# UKU20710_power_board.net
KiCad netlist of a schematic drawn in Altium Designer
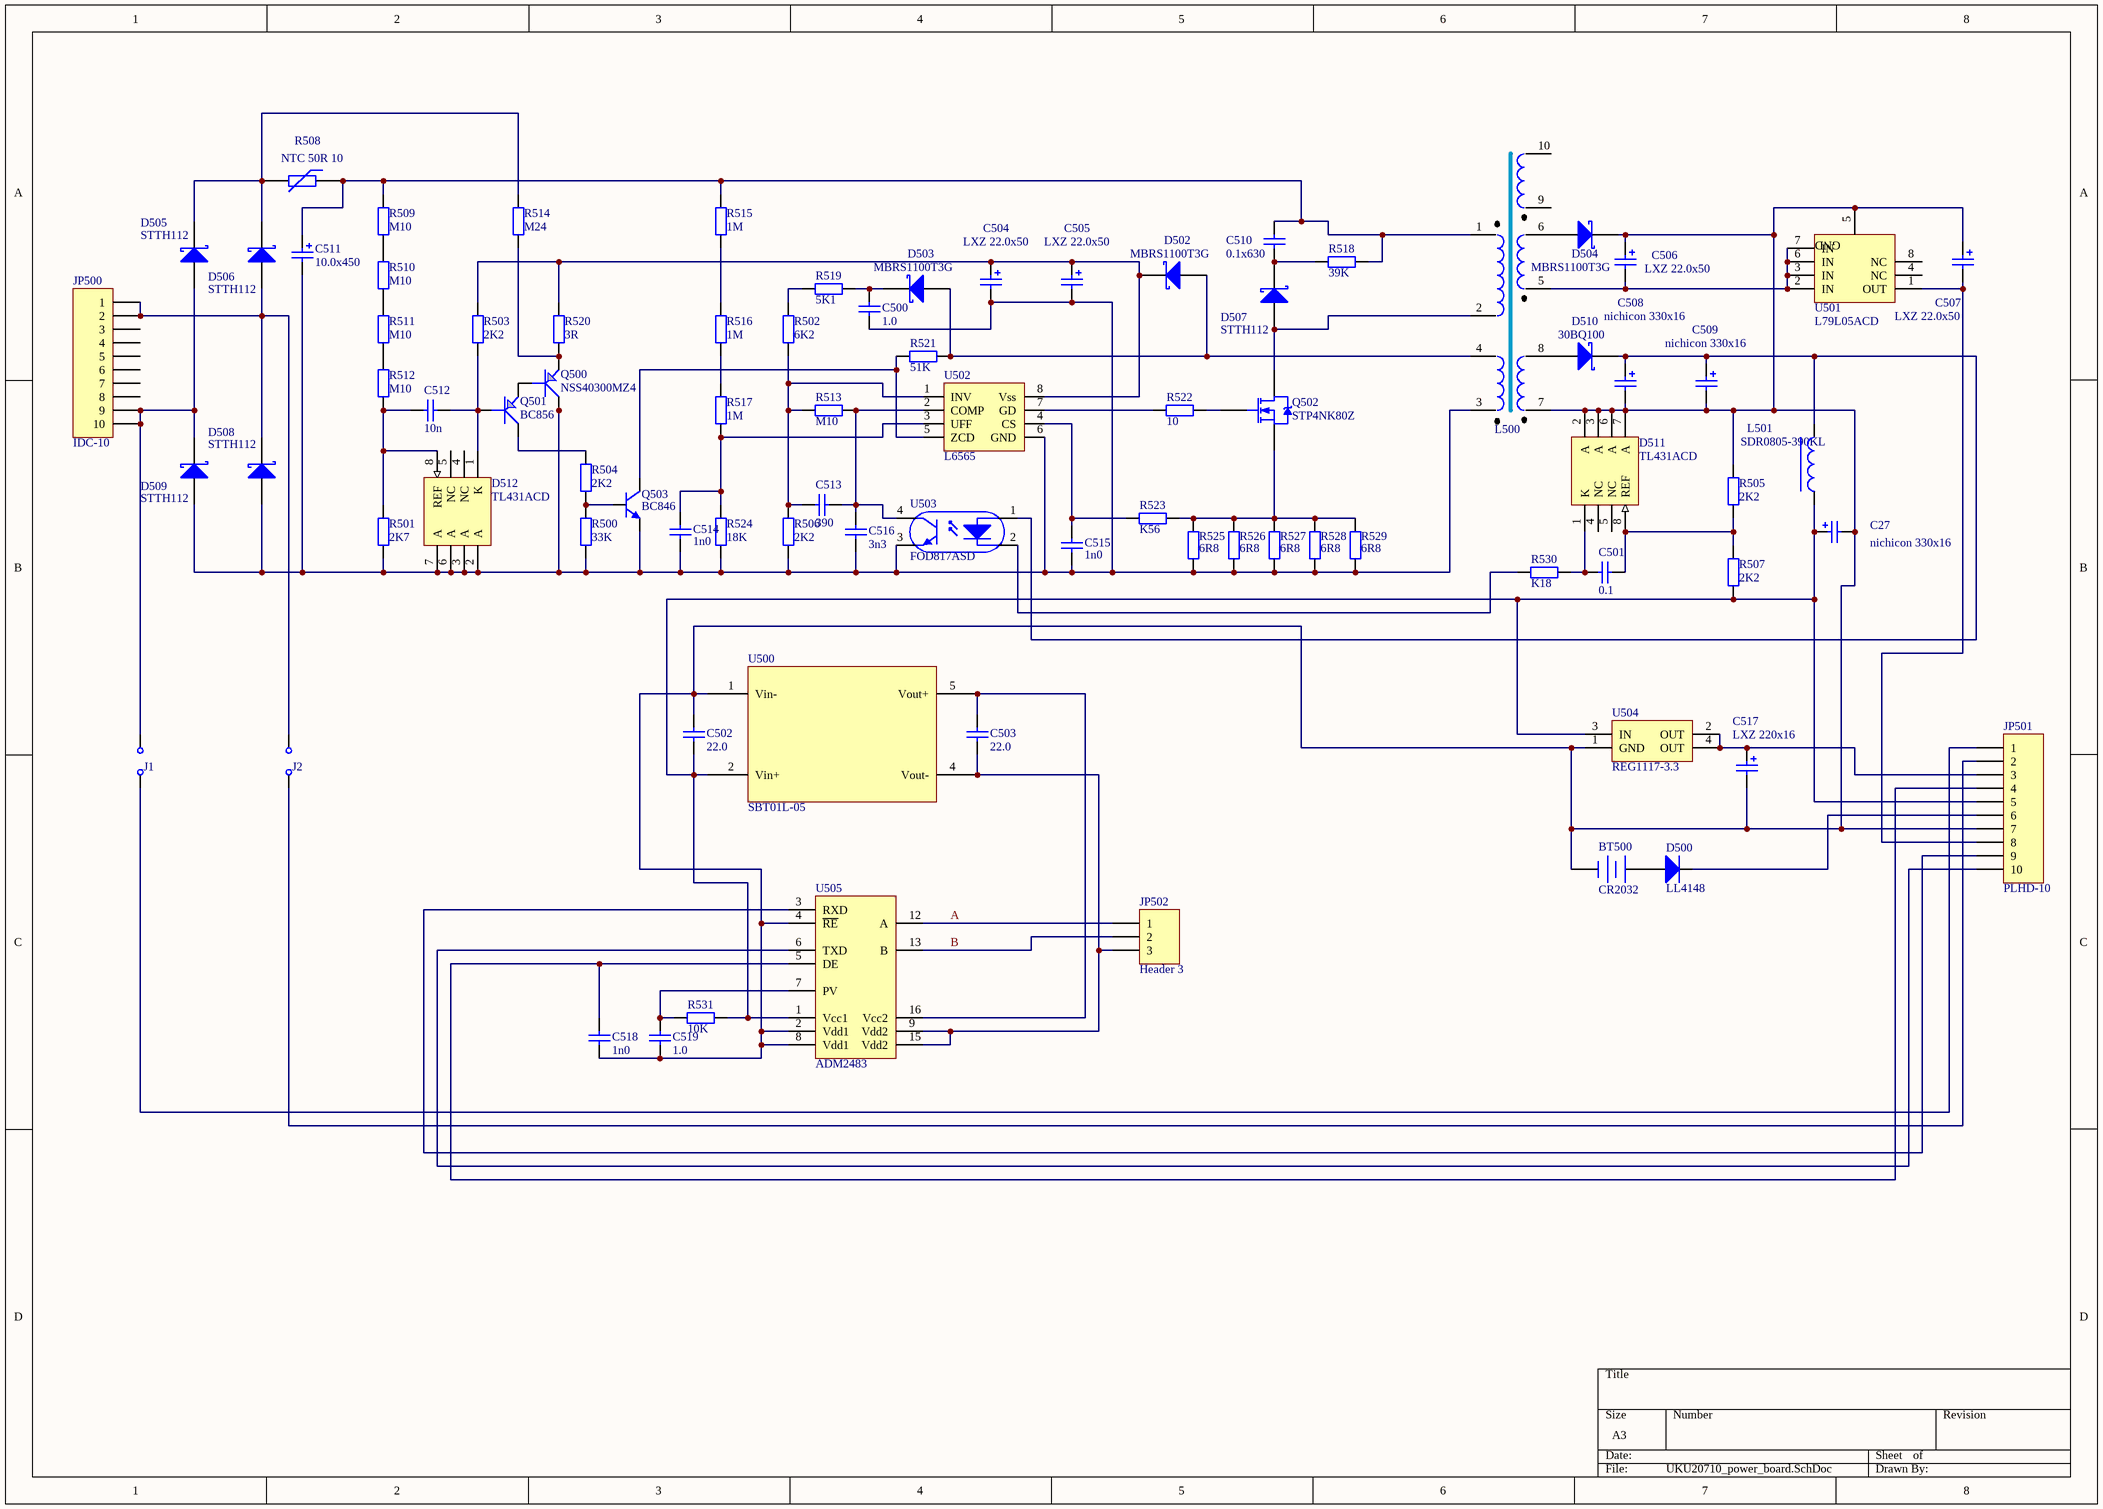
[diagram p0: UKU20710_power_board.SchDoc]

(export (version "E")
  (design (tool "Eeschema 10.0.6"))
  (components
    (comp (ref "BT500")
      (value "CR2032")
      (footprint "BAT_SUPP")
      (description "Multicell Battery")
      (fields (field (name "MANUFACTURER") "Generic Components") (field (name "PUBLISHER") "Altium Limited"))
      (libsource (lib "Miscellaneous Devices") (part "Battery"))
    )
    (comp (ref "C27")
      (value "nichicon 330x16")
      (footprint "el3")
      (description "Polarized Capacitor (Radial)")
      (fields (field (name "MANUFACTURER") "Generic Components") (field (name "PUBLISHER") "Altium Limited"))
      (libsource (lib "PAL") (part "Cap Pol1"))
    )
    (comp (ref "C500")
      (value "1.0")
      (footprint "_1206")
      (description "Capacitor (Semiconductor SIM Model)")
      (fields (field (name "MANUFACTURER") "Generic Components") (field (name "PUBLISHER") "Altium Limited"))
      (libsource (lib "Miscellaneous Devices") (part "Cap Semi"))
    )
    (comp (ref "C501")
      (value "0.1")
      (footprint "_1206")
      (description "Capacitor (Semiconductor SIM Model)")
      (fields (field (name "MANUFACTURER") "Generic Components") (field (name "PUBLISHER") "Altium Limited"))
      (libsource (lib "Miscellaneous Devices") (part "Cap Semi"))
    )
    (comp (ref "C502")
      (value "22.0")
      (footprint "_1206")
      (description "Capacitor (Semiconductor SIM Model)")
      (fields (field (name "MANUFACTURER") "Generic Components") (field (name "PUBLISHER") "Altium Limited"))
      (libsource (lib "Miscellaneous Devices") (part "Cap Semi"))
    )
    (comp (ref "C503")
      (value "22.0")
      (footprint "_1206")
      (description "Capacitor (Semiconductor SIM Model)")
      (fields (field (name "MANUFACTURER") "Generic Components") (field (name "PUBLISHER") "Altium Limited"))
      (libsource (lib "Miscellaneous Devices") (part "Cap Semi"))
    )
    (comp (ref "C504")
      (value "LXZ 22.0x50")
      (footprint "el3")
      (description "Polarized Capacitor (Radial)")
      (fields (field (name "MANUFACTURER") "Generic Components") (field (name "PUBLISHER") "Altium Limited"))
      (libsource (lib "PAL") (part "Cap Pol1"))
    )
    (comp (ref "C505")
      (value "LXZ 22.0x50")
      (footprint "el3")
      (description "Polarized Capacitor (Radial)")
      (fields (field (name "MANUFACTURER") "Generic Components") (field (name "PUBLISHER") "Altium Limited"))
      (libsource (lib "PAL") (part "Cap Pol1"))
    )
    (comp (ref "C506")
      (value "LXZ 22.0x50")
      (footprint "el3")
      (description "Polarized Capacitor (Radial)")
      (fields (field (name "MANUFACTURER") "Generic Components") (field (name "PUBLISHER") "Altium Limited"))
      (libsource (lib "PAL") (part "Cap Pol1"))
    )
    (comp (ref "C507")
      (value "LXZ 22.0x50")
      (footprint "el3")
      (description "Polarized Capacitor (Radial)")
      (fields (field (name "MANUFACTURER") "Generic Components") (field (name "PUBLISHER") "Altium Limited"))
      (libsource (lib "PAL") (part "Cap Pol1"))
    )
    (comp (ref "C508")
      (value "nichicon 330x16")
      (footprint "el3")
      (description "Polarized Capacitor (Radial)")
      (fields (field (name "MANUFACTURER") "Generic Components") (field (name "PUBLISHER") "Altium Limited"))
      (libsource (lib "PAL") (part "Cap Pol1"))
    )
    (comp (ref "C509")
      (value "nichicon 330x16")
      (footprint "el3")
      (description "Polarized Capacitor (Radial)")
      (fields (field (name "MANUFACTURER") "Generic Components") (field (name "PUBLISHER") "Altium Limited"))
      (libsource (lib "PAL") (part "Cap Pol1"))
    )
    (comp (ref "C510")
      (value "0.1x630")
      (footprint "c15")
      (description "Capacitor (Semiconductor SIM Model)")
      (fields (field (name "MANUFACTURER") "Generic Components") (field (name "PUBLISHER") "Altium Limited"))
      (libsource (lib "Miscellaneous Devices") (part "Cap Semi"))
    )
    (comp (ref "C511")
      (value "10.0x450")
      (footprint "el_15_25_h")
      (description "Polarized Capacitor (Radial)")
      (fields (field (name "MANUFACTURER") "Generic Components") (field (name "PUBLISHER") "Altium Limited"))
      (libsource (lib "PAL") (part "Cap Pol1"))
    )
    (comp (ref "C512")
      (value "10n")
      (footprint "_1206")
      (description "Capacitor (Semiconductor SIM Model)")
      (fields (field (name "MANUFACTURER") "Generic Components") (field (name "PUBLISHER") "Altium Limited"))
      (libsource (lib "Miscellaneous Devices") (part "Cap Semi"))
    )
    (comp (ref "C513")
      (value "390")
      (footprint "_1206")
      (description "Capacitor (Semiconductor SIM Model)")
      (fields (field (name "MANUFACTURER") "Generic Components") (field (name "PUBLISHER") "Altium Limited"))
      (libsource (lib "Miscellaneous Devices") (part "Cap Semi"))
    )
    (comp (ref "C514")
      (value "1n0")
      (footprint "_1206")
      (description "Capacitor (Semiconductor SIM Model)")
      (fields (field (name "MANUFACTURER") "Generic Components") (field (name "PUBLISHER") "Altium Limited"))
      (libsource (lib "Miscellaneous Devices") (part "Cap Semi"))
    )
    (comp (ref "C515")
      (value "1n0")
      (footprint "_1206")
      (description "Capacitor (Semiconductor SIM Model)")
      (fields (field (name "MANUFACTURER") "Generic Components") (field (name "PUBLISHER") "Altium Limited"))
      (libsource (lib "Miscellaneous Devices") (part "Cap Semi"))
    )
    (comp (ref "C516")
      (value "3n3")
      (footprint "_1206")
      (description "Capacitor (Semiconductor SIM Model)")
      (fields (field (name "MANUFACTURER") "Generic Components") (field (name "PUBLISHER") "Altium Limited"))
      (libsource (lib "Miscellaneous Devices") (part "Cap Semi"))
    )
    (comp (ref "C517")
      (value "LXZ 220x16")
      (footprint "el3")
      (description "Polarized Capacitor (Radial)")
      (fields (field (name "MANUFACTURER") "Generic Components") (field (name "PUBLISHER") "Altium Limited"))
      (libsource (lib "PAL") (part "Cap Pol1"))
    )
    (comp (ref "C518")
      (value "1n0")
      (footprint "_1206")
      (description "Capacitor (Semiconductor SIM Model)")
      (fields (field (name "MANUFACTURER") "Generic Components") (field (name "PUBLISHER") "Altium Limited"))
      (libsource (lib "Miscellaneous Devices") (part "Cap Semi"))
    )
    (comp (ref "C519")
      (value "1.0")
      (footprint "_1206")
      (description "Capacitor (Semiconductor SIM Model)")
      (fields (field (name "MANUFACTURER") "Generic Components") (field (name "PUBLISHER") "Altium Limited"))
      (libsource (lib "Miscellaneous Devices") (part "Cap Semi"))
    )
    (comp (ref "D500")
      (value "LL4148")
      (footprint "_1206d")
      (description "Default Diode")
      (fields (field (name "MANUFACTURER") "Generic Components") (field (name "PUBLISHER") "Altium Limited"))
      (libsource (lib "PAL") (part "Diode"))
    )
    (comp (ref "D502")
      (value "MBRS1100T3G")
      (footprint "D_6_3")
      (description "Schottky Rectifier")
      (fields
        (field (name "MANUFACTURER") "International Rectifier")
        (field (name "PUBLISHER") "Altium Limited")
      )
      (libsource (lib "IR Discrete Diode") (part "10BQ015"))
    )
    (comp (ref "D503")
      (value "MBRS1100T3G")
      (footprint "D_6_3")
      (description "Schottky Rectifier")
      (fields
        (field (name "MANUFACTURER") "International Rectifier")
        (field (name "PUBLISHER") "Altium Limited")
      )
      (libsource (lib "IR Discrete Diode") (part "10BQ015"))
    )
    (comp (ref "D504")
      (value "MBRS1100T3G")
      (footprint "D_6_3")
      (description "Schottky Rectifier")
      (fields
        (field (name "MANUFACTURER") "International Rectifier")
        (field (name "PUBLISHER") "Altium Limited")
      )
      (libsource (lib "IR Discrete Diode") (part "10BQ015"))
    )
    (comp (ref "D505")
      (value "STTH112")
      (footprint "D_6_3")
      (description "Schottky Diode")
      (fields
        (field (name "MANUFACTURER") "International Rectifier")
        (field (name "PUBLISHER") "Altium Limited")
      )
      (libsource (lib "IR Discrete Diode") (part "10BQ015"))
    )
    (comp (ref "D506")
      (value "STTH112")
      (footprint "D_6_3")
      (description "Schottky Diode")
      (fields
        (field (name "MANUFACTURER") "International Rectifier")
        (field (name "PUBLISHER") "Altium Limited")
      )
      (libsource (lib "IR Discrete Diode") (part "10BQ015"))
    )
    (comp (ref "D507")
      (value "STTH112")
      (footprint "D_6_3")
      (description "Schottky Diode")
      (fields
        (field (name "MANUFACTURER") "International Rectifier")
        (field (name "PUBLISHER") "Altium Limited")
      )
      (libsource (lib "IR Discrete Diode") (part "10BQ015"))
    )
    (comp (ref "D508")
      (value "STTH112")
      (footprint "D_6_3")
      (description "Schottky Diode")
      (fields
        (field (name "MANUFACTURER") "International Rectifier")
        (field (name "PUBLISHER") "Altium Limited")
      )
      (libsource (lib "IR Discrete Diode") (part "10BQ015"))
    )
    (comp (ref "D509")
      (value "STTH112")
      (footprint "D_6_3")
      (description "Schottky Diode")
      (fields
        (field (name "MANUFACTURER") "International Rectifier")
        (field (name "PUBLISHER") "Altium Limited")
      )
      (libsource (lib "IR Discrete Diode") (part "10BQ015"))
    )
    (comp (ref "D510")
      (value "30BQ100")
      (footprint "30BQ100")
      (description "Schottky Rectifier")
      (fields
        (field (name "MANUFACTURER") "International Rectifier")
        (field (name "PUBLISHER") "Altium Limited")
      )
      (libsource (lib "IR Discrete Diode") (part "10BQ015"))
    )
    (comp (ref "D511")
      (value "TL431ACD")
      (footprint "SO-G8")
      (description "Programmable Precision Reference")
      (fields (field (name "MANUFACTURER") "Motorola") (field (name "PUBLISHER") "Altium Limited"))
      (libsource (lib "") (part "TL431ACD_1"))
    )
    (comp (ref "D512")
      (value "TL431ACD")
      (footprint "SO-G8")
      (description "Programmable Precision Reference")
      (fields (field (name "MANUFACTURER") "Motorola") (field (name "PUBLISHER") "Altium Limited"))
      (libsource (lib "Motorola Power Management Voltage Reference") (part "TL431ACD"))
    )
    (comp (ref "J1")
      (value "~")
      (footprint "BT5-2")
      (description "Switch")
      (fields (field (name "MANUFACTURER") "Generic Components") (field (name "PUBLISHER") "Altium Limited"))
      (libsource (lib "PAL") (part "JMP"))
    )
    (comp (ref "J2")
      (value "~")
      (footprint "BT5-2")
      (description "Switch")
      (fields (field (name "MANUFACTURER") "Generic Components") (field (name "PUBLISHER") "Altium Limited"))
      (libsource (lib "PAL") (part "JMP"))
    )
    (comp (ref "JP500")
      (value "IDC-10")
      (footprint "HDR2X5")
      (description "Header, 10-Pin")
      (fields (field (name "MANUFACTURER") "Generic Components") (field (name "PUBLISHER") "Altium Limited"))
      (libsource (lib "") (part "Header 10_1"))
    )
    (comp (ref "JP501")
      (value "PLHD-10")
      (footprint "HDR2X5")
      (description "Header, 10-Pin")
      (fields (field (name "MANUFACTURER") "Generic Components") (field (name "PUBLISHER") "Altium Limited"))
      (libsource (lib "Miscellaneous Connectors") (part "Header 10"))
    )
    (comp (ref "JP502")
      (value "Header 3")
      (footprint "2EDG-5.08-3P")
      (description "Header, 3-Pin")
      (fields (field (name "MANUFACTURER") "Generic Components") (field (name "PUBLISHER") "Altium Limited"))
      (libsource (lib "Miscellaneous Connectors") (part "Header 3"))
    )
    (comp (ref "L500")
      (value "L220-K10")
      (footprint "trans_ring1")
      (description "Дроссель")
      (libsource (lib "PAL") (part "L1_dc_2"))
    )
    (comp (ref "L501")
      (value "SDR0805-390KL")
      (footprint "L10x10")
      (description "Magnetic-Core Inductor")
      (fields (field (name "MANUFACTURER") "Generic Components") (field (name "PUBLISHER") "Altium Limited"))
      (libsource (lib "PAL") (part "Inductor Konstr 2"))
    )
    (comp (ref "Q500")
      (value "NSS40300MZ4")
      (footprint "DSO-G3")
      (libsource (lib "PAL") (part "NSS40300MZ4"))
    )
    (comp (ref "Q501")
      (value "BC856")
      (footprint "SO-G3")
      (description "Bipolar transistor")
      (libsource (lib "MAIN") (part "GT109"))
    )
    (comp (ref "Q502")
      (value "STP4NK80Z")
      (footprint "TO220_h")
      (description "N-Channel Power MOSFET")
      (fields (field (name "MANUFACTURER") "Generic Components") (field (name "PUBLISHER") "Altium Limited"))
      (libsource (lib "Miscellaneous Devices") (part "NMOS-2"))
    )
    (comp (ref "Q503")
      (value "BC846")
      (footprint "SO-G3")
      (description "General Purpose Transistor NPN Silicon")
      (fields (field (name "MANUFACTURER") "Motorola") (field (name "PUBLISHER") "Altium Limited"))
      (libsource (lib "PAL") (part "BC847ALT1"))
    )
    (comp (ref "R500")
      (value "33K")
      (footprint "_1206")
      (description "Resistor")
      (fields (field (name "MANUFACTURER") "Generic Components") (field (name "PUBLISHER") "Altium Limited"))
      (libsource (lib "") (part "Res2_2"))
    )
    (comp (ref "R501")
      (value "2K7")
      (footprint "_1206")
      (description "Resistor")
      (fields (field (name "MANUFACTURER") "Generic Components") (field (name "PUBLISHER") "Altium Limited"))
      (libsource (lib "") (part "Res2_2"))
    )
    (comp (ref "R502")
      (value "6K2")
      (footprint "_1206")
      (description "Resistor")
      (fields (field (name "MANUFACTURER") "Generic Components") (field (name "PUBLISHER") "Altium Limited"))
      (libsource (lib "") (part "Res2_2"))
    )
    (comp (ref "R503")
      (value "2K2")
      (footprint "_1206")
      (description "Resistor")
      (fields (field (name "MANUFACTURER") "Generic Components") (field (name "PUBLISHER") "Altium Limited"))
      (libsource (lib "") (part "Res2_2"))
    )
    (comp (ref "R504")
      (value "2K2")
      (footprint "_1206")
      (description "Resistor")
      (fields (field (name "MANUFACTURER") "Generic Components") (field (name "PUBLISHER") "Altium Limited"))
      (libsource (lib "") (part "Res2_2"))
    )
    (comp (ref "R505")
      (value "2K2")
      (footprint "_1206")
      (description "Resistor")
      (fields (field (name "MANUFACTURER") "Generic Components") (field (name "PUBLISHER") "Altium Limited"))
      (libsource (lib "") (part "Res2_2"))
    )
    (comp (ref "R506")
      (value "2K2")
      (footprint "_1206")
      (description "Resistor")
      (fields (field (name "MANUFACTURER") "Generic Components") (field (name "PUBLISHER") "Altium Limited"))
      (libsource (lib "") (part "Res2_2"))
    )
    (comp (ref "R507")
      (value "2K2")
      (footprint "_1206")
      (description "Resistor")
      (fields (field (name "MANUFACTURER") "Generic Components") (field (name "PUBLISHER") "Altium Limited"))
      (libsource (lib "") (part "Res2_2"))
    )
    (comp (ref "R508")
      (value "NTC 50R 10")
      (footprint "JVR07N")
      (description "Varistor (Voltage-Sensitive Resistor)")
      (fields (field (name "MANUFACTURER") "Generic Components") (field (name "PUBLISHER") "Altium Limited"))
      (libsource (lib "Miscellaneous Devices") (part "Res Varistor"))
    )
    (comp (ref "R509")
      (value "M10")
      (footprint "_1206")
      (description "Resistor")
      (fields (field (name "MANUFACTURER") "Generic Components") (field (name "PUBLISHER") "Altium Limited"))
      (libsource (lib "") (part "Res2_2"))
    )
    (comp (ref "R510")
      (value "M10")
      (footprint "_1206")
      (description "Resistor")
      (fields (field (name "MANUFACTURER") "Generic Components") (field (name "PUBLISHER") "Altium Limited"))
      (libsource (lib "") (part "Res2_2"))
    )
    (comp (ref "R511")
      (value "M10")
      (footprint "_1206")
      (description "Resistor")
      (fields (field (name "MANUFACTURER") "Generic Components") (field (name "PUBLISHER") "Altium Limited"))
      (libsource (lib "") (part "Res2_2"))
    )
    (comp (ref "R512")
      (value "M10")
      (footprint "_1206")
      (description "Resistor")
      (fields (field (name "MANUFACTURER") "Generic Components") (field (name "PUBLISHER") "Altium Limited"))
      (libsource (lib "") (part "Res2_2"))
    )
    (comp (ref "R513")
      (value "M10")
      (footprint "_1206")
      (description "Resistor")
      (fields (field (name "MANUFACTURER") "Generic Components") (field (name "PUBLISHER") "Altium Limited"))
      (libsource (lib "Miscellaneous Devices") (part "Res2"))
    )
    (comp (ref "R514")
      (value "M24")
      (footprint "AXIAL-0.7")
      (description "Resistor")
      (fields (field (name "MANUFACTURER") "Generic Components") (field (name "PUBLISHER") "Altium Limited"))
      (libsource (lib "") (part "Res2_2"))
    )
    (comp (ref "R515")
      (value "1M")
      (footprint "_1206")
      (description "Resistor")
      (fields (field (name "MANUFACTURER") "Generic Components") (field (name "PUBLISHER") "Altium Limited"))
      (libsource (lib "") (part "Res2_2"))
    )
    (comp (ref "R516")
      (value "1M")
      (footprint "_1206")
      (description "Resistor")
      (fields (field (name "MANUFACTURER") "Generic Components") (field (name "PUBLISHER") "Altium Limited"))
      (libsource (lib "") (part "Res2_2"))
    )
    (comp (ref "R517")
      (value "1M")
      (footprint "_1206")
      (description "Resistor")
      (fields (field (name "MANUFACTURER") "Generic Components") (field (name "PUBLISHER") "Altium Limited"))
      (libsource (lib "") (part "Res2_2"))
    )
    (comp (ref "R518")
      (value "39K")
      (footprint "AXIAL-0.7")
      (description "Resistor")
      (fields (field (name "MANUFACTURER") "Generic Components") (field (name "PUBLISHER") "Altium Limited"))
      (libsource (lib "Miscellaneous Devices") (part "Res2"))
    )
    (comp (ref "R519")
      (value "5K1")
      (footprint "_1206")
      (description "Resistor")
      (fields (field (name "MANUFACTURER") "Generic Components") (field (name "PUBLISHER") "Altium Limited"))
      (libsource (lib "Miscellaneous Devices") (part "Res2"))
    )
    (comp (ref "R520")
      (value "3R")
      (footprint "_1206")
      (description "Resistor")
      (fields (field (name "MANUFACTURER") "Generic Components") (field (name "PUBLISHER") "Altium Limited"))
      (libsource (lib "") (part "Res2_2"))
    )
    (comp (ref "R521")
      (value "51K")
      (footprint "_1206")
      (description "Resistor")
      (fields (field (name "MANUFACTURER") "Generic Components") (field (name "PUBLISHER") "Altium Limited"))
      (libsource (lib "Miscellaneous Devices") (part "Res2"))
    )
    (comp (ref "R522")
      (value "10")
      (footprint "_1206")
      (description "Resistor")
      (fields (field (name "MANUFACTURER") "Generic Components") (field (name "PUBLISHER") "Altium Limited"))
      (libsource (lib "Miscellaneous Devices") (part "Res2"))
    )
    (comp (ref "R523")
      (value "K56")
      (footprint "_1206")
      (description "Resistor")
      (fields (field (name "MANUFACTURER") "Generic Components") (field (name "PUBLISHER") "Altium Limited"))
      (libsource (lib "Miscellaneous Devices") (part "Res2"))
    )
    (comp (ref "R524")
      (value "18K")
      (footprint "_1206")
      (description "Resistor")
      (fields (field (name "MANUFACTURER") "Generic Components") (field (name "PUBLISHER") "Altium Limited"))
      (libsource (lib "") (part "Res2_2"))
    )
    (comp (ref "R525")
      (value "6R8")
      (footprint "_1206")
      (description "Resistor")
      (fields (field (name "MANUFACTURER") "Generic Components") (field (name "PUBLISHER") "Altium Limited"))
      (libsource (lib "") (part "Res2_1"))
    )
    (comp (ref "R526")
      (value "6R8")
      (footprint "_1206")
      (description "Resistor")
      (fields (field (name "MANUFACTURER") "Generic Components") (field (name "PUBLISHER") "Altium Limited"))
      (libsource (lib "") (part "Res2_1"))
    )
    (comp (ref "R527")
      (value "6R8")
      (footprint "_1206")
      (description "Resistor")
      (fields (field (name "MANUFACTURER") "Generic Components") (field (name "PUBLISHER") "Altium Limited"))
      (libsource (lib "") (part "Res2_1"))
    )
    (comp (ref "R528")
      (value "6R8")
      (footprint "_1206")
      (description "Resistor")
      (fields (field (name "MANUFACTURER") "Generic Components") (field (name "PUBLISHER") "Altium Limited"))
      (libsource (lib "") (part "Res2_1"))
    )
    (comp (ref "R529")
      (value "6R8")
      (footprint "_1206")
      (description "Resistor")
      (fields (field (name "MANUFACTURER") "Generic Components") (field (name "PUBLISHER") "Altium Limited"))
      (libsource (lib "") (part "Res2_1"))
    )
    (comp (ref "R530")
      (value "K18")
      (footprint "_1206")
      (description "Resistor")
      (fields (field (name "MANUFACTURER") "Generic Components") (field (name "PUBLISHER") "Altium Limited"))
      (libsource (lib "Miscellaneous Devices") (part "Res2"))
    )
    (comp (ref "R531")
      (value "10K")
      (footprint "_1206")
      (description "Resistor")
      (fields (field (name "MANUFACTURER") "Generic Components") (field (name "PUBLISHER") "Altium Limited"))
      (libsource (lib "Miscellaneous Devices") (part "Res2"))
    )
    (comp (ref "U500") (value "SBT01L-05") (footprint "SBT01DET01") (libsource (lib "PAL") (part "SBT01L")))
    (comp (ref "U501")
      (value "L79L05ACD")
      (footprint "SO-G8")
      (description "Negative Voltage Regulator")
      (fields (field (name "MANUFACTURER") "ST-Microelectronics") (field (name "PUBLISHER") "Altium Limited"))
      (libsource (lib "ST Power Mgt Voltage Regulator") (part "L79L05ACD"))
    )
    (comp (ref "U502") (value "L6565") (footprint "so-g8") (libsource (lib "PAL") (part "L6565")))
    (comp (ref "U503") (value "FOD817ASD") (footprint "FOD817ASD") (libsource (lib "PAL") (part "F00817ASD")))
    (comp (ref "U504")
      (value "REG1117-3.3")
      (footprint "DSO-G3")
      (description "800mA and 1A Low Dropout Positive Regulator 2.85V, 3.3V, 5V, and Adjustable")
      (fields (field (name "MANUFACTURER") "Burr-Brown") (field (name "PUBLISHER") "Altium Limited"))
      (libsource (lib "BB Power Mgt Voltage Regulator") (part "REG1117-3.3"))
    )
    (comp (ref "U505") (value "ADM2483") (footprint "SO-G16/D10.4") (libsource (lib "PAL") (part "ADM2483")))
  )
  (nets
    (net (code "1") (name "/A") (class "Default")
      (node (ref "JP502") (pin "1") (pinfunction "1_1") (pintype "passive"))
      (node (ref "U505") (pin "12") (pinfunction "A_12") (pintype "passive"))
    )
    (net (code "2") (name "/B") (class "Default")
      (node (ref "JP502") (pin "2") (pinfunction "2_2") (pintype "passive"))
      (node (ref "U505") (pin "13") (pinfunction "B_13") (pintype "passive"))
    )
    (net (code "3") (name "Net-(BT500-+)") (class "Default")
      (node (ref "BT500") (pin "1") (pinfunction "+_1") (pintype "passive"))
      (node (ref "D500") (pin "1") (pinfunction "A_1") (pintype "passive"))
    )
    (net (code "4") (name "Net-(BT500--)") (class "Default")
      (node (ref "BT500") (pin "2") (pinfunction "-_2") (pintype "passive"))
      (node (ref "C27") (pin "2") (pinfunction "2_2") (pintype "passive"))
      (node (ref "C502") (pin "1") (pinfunction "1_1") (pintype "passive"))
      (node (ref "C506") (pin "1") (pinfunction "1_1") (pintype "passive"))
      (node (ref "C507") (pin "1") (pinfunction "1_1") (pintype "passive"))
      (node (ref "C508") (pin "2") (pinfunction "2_2") (pintype "passive"))
      (node (ref "C509") (pin "2") (pinfunction "2_2") (pintype "passive"))
      (node (ref "C517") (pin "2") (pinfunction "2_2") (pintype "passive"))
      (node (ref "C518") (pin "1") (pinfunction "1_1") (pintype "passive"))
      (node (ref "C519") (pin "1") (pinfunction "1_1") (pintype "passive"))
      (node (ref "D504") (pin "2") (pinfunction "K_2") (pintype "passive"))
      (node (ref "D511") (pin "2") (pinfunction "A_2") (pintype "passive"))
      (node (ref "D511") (pin "3") (pinfunction "A_3") (pintype "passive"))
      (node (ref "D511") (pin "6") (pinfunction "A_6") (pintype "passive"))
      (node (ref "D511") (pin "7") (pinfunction "A_7") (pintype "passive"))
      (node (ref "JP501") (pin "7") (pinfunction "7_7") (pintype "passive"))
      (node (ref "L500") (pin "7") (pintype "passive"))
      (node (ref "R505") (pin "2") (pinfunction "2_2") (pintype "passive"))
      (node (ref "U500") (pin "1") (pinfunction "Vin-_1") (pintype "passive"))
      (node (ref "U501") (pin "5") (pinfunction "GND_5") (pintype "power_in"))
      (node (ref "U504") (pin "1") (pinfunction "GND_1") (pintype "power_in"))
      (node (ref "U505") (pin "2") (pinfunction "Vdd1_2") (pintype "passive"))
      (node (ref "U505") (pin "4") (pinfunction "~{RE}_4") (pintype "passive"))
      (node (ref "U505") (pin "8") (pinfunction "Vdd1_8") (pintype "passive"))
    )
    (net (code "5") (name "Net-(C506-Pad2)") (class "Default")
      (node (ref "C506") (pin "2") (pinfunction "2_2") (pintype "passive"))
      (node (ref "L500") (pin "5") (pintype "passive"))
      (node (ref "U501") (pin "2") (pinfunction "IN_2") (pintype "power_in"))
      (node (ref "U501") (pin "3") (pinfunction "IN_3") (pintype "power_in"))
      (node (ref "U501") (pin "6") (pinfunction "IN_6") (pintype "power_in"))
      (node (ref "U501") (pin "7") (pinfunction "IN_7") (pintype "power_in"))
    )
    (net (code "6") (name "Net-(C510-Pad2)") (class "Default")
      (node (ref "C510") (pin "2") (pinfunction "2_2") (pintype "passive"))
      (node (ref "C511") (pin "1") (pinfunction "1_1") (pintype "passive"))
      (node (ref "L500") (pin "1") (pintype "passive"))
      (node (ref "R508") (pin "1") (pinfunction "1_1") (pintype "passive"))
      (node (ref "R509") (pin "2") (pinfunction "2_2") (pintype "passive"))
      (node (ref "R515") (pin "2") (pinfunction "2_2") (pintype "passive"))
      (node (ref "R518") (pin "1") (pinfunction "1_1") (pintype "passive"))
    )
    (net (code "7") (name "Net-(C517-Pad1)") (class "Default")
      (node (ref "C517") (pin "1") (pinfunction "1_1") (pintype "passive"))
      (node (ref "JP501") (pin "3") (pinfunction "3_3") (pintype "passive"))
      (node (ref "U504") (pin "2") (pinfunction "OUT_2") (pintype "power_in"))
      (node (ref "U504") (pin "4") (pinfunction "OUT_4") (pintype "power_in"))
    )
    (net (code "8") (name "Net-(D500-K)") (class "Default")
      (node (ref "D500") (pin "2") (pinfunction "K_2") (pintype "passive"))
      (node (ref "JP501") (pin "6") (pinfunction "6_6") (pintype "passive"))
    )
    (net (code "9") (name "Net-(D502-A)") (class "Default")
      (node (ref "D502") (pin "1") (pinfunction "A_1") (pintype "passive"))
      (node (ref "D503") (pin "1") (pinfunction "A_1") (pintype "passive"))
      (node (ref "L500") (pin "4") (pintype "passive"))
      (node (ref "R521") (pin "1") (pinfunction "1_1") (pintype "passive"))
    )
    (net (code "10") (name "Net-(D502-K)") (class "Default")
      (node (ref "C504") (pin "1") (pinfunction "1_1") (pintype "passive"))
      (node (ref "C505") (pin "1") (pinfunction "1_1") (pintype "passive"))
      (node (ref "D502") (pin "2") (pinfunction "K_2") (pintype "passive"))
      (node (ref "R503") (pin "2") (pinfunction "2_2") (pintype "passive"))
      (node (ref "R520") (pin "2") (pinfunction "2_2") (pintype "passive"))
      (node (ref "U502") (pin "8") (pinfunction "Vss_8") (pintype "passive"))
    )
    (net (code "11") (name "Net-(D503-K)") (class "Default")
      (node (ref "C500") (pin "2") (pinfunction "2_2") (pintype "passive"))
      (node (ref "D503") (pin "2") (pinfunction "K_2") (pintype "passive"))
      (node (ref "R519") (pin "1") (pinfunction "1_1") (pintype "passive"))
    )
    (net (code "12") (name "Net-(D504-A)") (class "Default")
      (node (ref "D504") (pin "1") (pinfunction "A_1") (pintype "passive"))
      (node (ref "L500") (pin "6") (pintype "passive"))
    )
    (net (code "13") (name "Net-(D505-A)") (class "Default")
      (node (ref "D505") (pin "1") (pinfunction "A_1") (pintype "passive"))
      (node (ref "D509") (pin "2") (pinfunction "K_2") (pintype "passive"))
      (node (ref "J1") (pin "2") (pinfunction "2_2") (pintype "passive"))
      (node (ref "JP500") (pin "10") (pinfunction "10_10") (pintype "passive"))
      (node (ref "JP500") (pin "9") (pinfunction "9_9") (pintype "passive"))
    )
    (net (code "14") (name "Net-(D505-K)") (class "Default")
      (node (ref "D505") (pin "2") (pinfunction "K_2") (pintype "passive"))
      (node (ref "D506") (pin "2") (pinfunction "K_2") (pintype "passive"))
      (node (ref "R508") (pin "2") (pinfunction "2_2") (pintype "passive"))
      (node (ref "R514") (pin "2") (pinfunction "2_2") (pintype "passive"))
    )
    (net (code "15") (name "Net-(D506-A)") (class "Default")
      (node (ref "D506") (pin "1") (pinfunction "A_1") (pintype "passive"))
      (node (ref "D508") (pin "2") (pinfunction "K_2") (pintype "passive"))
      (node (ref "J2") (pin "2") (pinfunction "2_2") (pintype "passive"))
      (node (ref "JP500") (pin "1") (pinfunction "1_1") (pintype "passive"))
      (node (ref "JP500") (pin "2") (pinfunction "2_2") (pintype "passive"))
    )
    (net (code "16") (name "Net-(D507-A)") (class "Default")
      (node (ref "D507") (pin "1") (pinfunction "A_1") (pintype "passive"))
      (node (ref "L500") (pin "2") (pintype "passive"))
      (node (ref "Q502") (pin "2") (pinfunction "D_2") (pintype "passive"))
    )
    (net (code "17") (name "Net-(D507-K)") (class "Default")
      (node (ref "C510") (pin "1") (pinfunction "1_1") (pintype "passive"))
      (node (ref "D507") (pin "2") (pinfunction "K_2") (pintype "passive"))
      (node (ref "R518") (pin "2") (pinfunction "2_2") (pintype "passive"))
    )
    (net (code "18") (name "Net-(D508-A)") (class "Default")
      (node (ref "C500") (pin "1") (pinfunction "1_1") (pintype "passive"))
      (node (ref "C504") (pin "2") (pinfunction "2_2") (pintype "passive"))
      (node (ref "C505") (pin "2") (pinfunction "2_2") (pintype "passive"))
      (node (ref "C511") (pin "2") (pinfunction "2_2") (pintype "passive"))
      (node (ref "C514") (pin "2") (pinfunction "2_2") (pintype "passive"))
      (node (ref "C515") (pin "2") (pinfunction "2_2") (pintype "passive"))
      (node (ref "C516") (pin "1") (pinfunction "1_1") (pintype "passive"))
      (node (ref "D508") (pin "1") (pinfunction "A_1") (pintype "passive"))
      (node (ref "D509") (pin "1") (pinfunction "A_1") (pintype "passive"))
      (node (ref "D512") (pin "2") (pinfunction "A_2") (pintype "passive"))
      (node (ref "D512") (pin "3") (pinfunction "A_3") (pintype "passive"))
      (node (ref "D512") (pin "6") (pinfunction "A_6") (pintype "passive"))
      (node (ref "D512") (pin "7") (pinfunction "A_7") (pintype "passive"))
      (node (ref "L500") (pin "3") (pintype "passive"))
      (node (ref "Q500") (pin "2") (pinfunction "C_2") (pintype "passive"))
      (node (ref "Q500") (pin "4") (pinfunction "C_4") (pintype "passive"))
      (node (ref "Q503") (pin "2") (pinfunction "E_2") (pintype "passive"))
      (node (ref "R500") (pin "1") (pinfunction "1_1") (pintype "passive"))
      (node (ref "R501") (pin "1") (pinfunction "1_1") (pintype "passive"))
      (node (ref "R506") (pin "1") (pinfunction "1_1") (pintype "passive"))
      (node (ref "R524") (pin "1") (pinfunction "1_1") (pintype "passive"))
      (node (ref "R525") (pin "2") (pinfunction "2_2") (pintype "passive"))
      (node (ref "R526") (pin "2") (pinfunction "2_2") (pintype "passive"))
      (node (ref "R527") (pin "2") (pinfunction "2_2") (pintype "passive"))
      (node (ref "R528") (pin "2") (pinfunction "2_2") (pintype "passive"))
      (node (ref "R529") (pin "2") (pinfunction "2_2") (pintype "passive"))
      (node (ref "U502") (pin "6") (pinfunction "GND_6") (pintype "passive"))
      (node (ref "U503") (pin "3") (pinfunction "4_3") (pintype "passive"))
    )
    (net (code "19") (name "Net-(D510-A)") (class "Default")
      (node (ref "D510") (pin "1") (pinfunction "A_1") (pintype "passive"))
      (node (ref "L500") (pin "8") (pintype "passive"))
    )
    (net (code "20") (name "Net-(D510-K)") (class "Default")
      (node (ref "C508") (pin "1") (pinfunction "1_1") (pintype "passive"))
      (node (ref "C509") (pin "1") (pinfunction "1_1") (pintype "passive"))
      (node (ref "D510") (pin "2") (pinfunction "K_2") (pintype "passive"))
      (node (ref "L501") (pin "2") (pinfunction "2_2") (pintype "passive"))
      (node (ref "U503") (pin "1") (pinfunction "0_1") (pintype "passive"))
    )
    (net (code "21") (name "Net-(D511-K)") (class "Default")
      (node (ref "C501") (pin "2") (pinfunction "2_2") (pintype "passive"))
      (node (ref "D511") (pin "1") (pinfunction "K_1") (pintype "passive"))
      (node (ref "R530") (pin "1") (pinfunction "1_1") (pintype "passive"))
    )
    (net (code "22") (name "Net-(D511-REF)") (class "Default")
      (node (ref "C501") (pin "1") (pinfunction "1_1") (pintype "passive"))
      (node (ref "D511") (pin "8") (pinfunction "REF_8") (pintype "input"))
      (node (ref "R505") (pin "1") (pinfunction "1_1") (pintype "passive"))
      (node (ref "R507") (pin "2") (pinfunction "2_2") (pintype "passive"))
    )
    (net (code "23") (name "Net-(D512-K)") (class "Default")
      (node (ref "C512") (pin "1") (pinfunction "1_1") (pintype "passive"))
      (node (ref "D512") (pin "1") (pinfunction "K_1") (pintype "passive"))
      (node (ref "Q501") (pin "1") (pinfunction "B_1") (pintype "passive"))
      (node (ref "R503") (pin "1") (pinfunction "1_1") (pintype "passive"))
    )
    (net (code "24") (name "Net-(D512-REF)") (class "Default")
      (node (ref "C512") (pin "2") (pinfunction "2_2") (pintype "passive"))
      (node (ref "D512") (pin "8") (pinfunction "REF_8") (pintype "input"))
      (node (ref "R501") (pin "2") (pinfunction "2_2") (pintype "passive"))
      (node (ref "R512") (pin "1") (pinfunction "1_1") (pintype "passive"))
    )
    (net (code "25") (name "Net-(J1-Pad1)") (class "Default")
      (node (ref "J1") (pin "1") (pinfunction "1_1") (pintype "passive"))
      (node (ref "JP501") (pin "1") (pinfunction "1_1") (pintype "passive"))
    )
    (net (code "26") (name "Net-(J2-Pad1)") (class "Default")
      (node (ref "J2") (pin "1") (pinfunction "1_1") (pintype "passive"))
      (node (ref "JP501") (pin "2") (pinfunction "2_2") (pintype "passive"))
    )
    (net (code "27") (name "Net-(Q500-B)") (class "Default")
      (node (ref "Q500") (pin "1") (pinfunction "B_1") (pintype "passive"))
      (node (ref "Q501") (pin "2") (pinfunction "E_2") (pintype "passive"))
    )
    (net (code "28") (name "Net-(Q500-E)") (class "Default")
      (node (ref "Q500") (pin "3") (pinfunction "E_3") (pintype "passive"))
      (node (ref "R514") (pin "1") (pinfunction "1_1") (pintype "passive"))
      (node (ref "R520") (pin "1") (pinfunction "1_1") (pintype "passive"))
    )
    (net (code "29") (name "Net-(Q501-C)") (class "Default")
      (node (ref "Q501") (pin "3") (pinfunction "C_3") (pintype "passive"))
      (node (ref "R504") (pin "2") (pinfunction "2_2") (pintype "passive"))
    )
    (net (code "30") (name "Net-(Q502-G)") (class "Default")
      (node (ref "Q502") (pin "1") (pinfunction "G_1") (pintype "passive"))
      (node (ref "R522") (pin "1") (pinfunction "1_1") (pintype "passive"))
    )
    (net (code "31") (name "Net-(Q502-S)") (class "Default")
      (node (ref "Q502") (pin "3") (pinfunction "S_3") (pintype "passive"))
      (node (ref "R523") (pin "1") (pinfunction "1_1") (pintype "passive"))
      (node (ref "R525") (pin "1") (pinfunction "1_1") (pintype "passive"))
      (node (ref "R526") (pin "1") (pinfunction "1_1") (pintype "passive"))
      (node (ref "R527") (pin "1") (pinfunction "1_1") (pintype "passive"))
      (node (ref "R528") (pin "1") (pinfunction "1_1") (pintype "passive"))
      (node (ref "R529") (pin "1") (pinfunction "1_1") (pintype "passive"))
    )
    (net (code "32") (name "Net-(Q503-B)") (class "Default")
      (node (ref "Q503") (pin "1") (pinfunction "B_1") (pintype "passive"))
      (node (ref "R500") (pin "2") (pinfunction "2_2") (pintype "passive"))
      (node (ref "R504") (pin "1") (pinfunction "1_1") (pintype "passive"))
    )
    (net (code "33") (name "Net-(Q503-C)") (class "Default")
      (node (ref "Q503") (pin "3") (pinfunction "C_3") (pintype "passive"))
      (node (ref "R521") (pin "2") (pinfunction "2_2") (pintype "passive"))
      (node (ref "U502") (pin "5") (pinfunction "ZCD_5") (pintype "passive"))
    )
    (net (code "34") (name "Net-(R502-Pad2)") (class "Default")
      (node (ref "R502") (pin "2") (pinfunction "2_2") (pintype "passive"))
      (node (ref "R519") (pin "2") (pinfunction "2_2") (pintype "passive"))
    )
    (net (code "35") (name "Net-(R509-Pad1)") (class "Default")
      (node (ref "R509") (pin "1") (pinfunction "1_1") (pintype "passive"))
      (node (ref "R510") (pin "2") (pinfunction "2_2") (pintype "passive"))
    )
    (net (code "36") (name "Net-(R510-Pad1)") (class "Default")
      (node (ref "R510") (pin "1") (pinfunction "1_1") (pintype "passive"))
      (node (ref "R511") (pin "2") (pinfunction "2_2") (pintype "passive"))
    )
    (net (code "37") (name "Net-(R511-Pad1)") (class "Default")
      (node (ref "R511") (pin "1") (pinfunction "1_1") (pintype "passive"))
      (node (ref "R512") (pin "2") (pinfunction "2_2") (pintype "passive"))
    )
    (net (code "38") (name "Net-(R515-Pad1)") (class "Default")
      (node (ref "R515") (pin "1") (pinfunction "1_1") (pintype "passive"))
      (node (ref "R516") (pin "2") (pinfunction "2_2") (pintype "passive"))
    )
    (net (code "39") (name "Net-(R516-Pad1)") (class "Default")
      (node (ref "R516") (pin "1") (pinfunction "1_1") (pintype "passive"))
      (node (ref "R517") (pin "2") (pinfunction "2_2") (pintype "passive"))
    )
    (net (code "40") (name "Net-(U500-Vin+)") (class "Default")
      (node (ref "C27") (pin "1") (pinfunction "1_1") (pintype "passive"))
      (node (ref "C502") (pin "2") (pinfunction "2_2") (pintype "passive"))
      (node (ref "JP501") (pin "5") (pinfunction "5_5") (pintype "passive"))
      (node (ref "L501") (pin "1") (pinfunction "1_1") (pintype "passive"))
      (node (ref "R507") (pin "1") (pinfunction "1_1") (pintype "passive"))
      (node (ref "R531") (pin "1") (pinfunction "1_1") (pintype "passive"))
      (node (ref "U500") (pin "2") (pinfunction "Vin+_2") (pintype "passive"))
      (node (ref "U504") (pin "3") (pinfunction "IN_3") (pintype "power_in"))
      (node (ref "U505") (pin "1") (pinfunction "Vcc1_1") (pintype "passive"))
    )
    (net (code "41") (name "Net-(U500-Vout+)") (class "Default")
      (node (ref "C503") (pin "1") (pinfunction "1_1") (pintype "passive"))
      (node (ref "U500") (pin "5") (pinfunction "Vout+_5") (pintype "passive"))
      (node (ref "U505") (pin "16") (pinfunction "Vcc2_16") (pintype "passive"))
    )
    (net (code "42") (name "Net-(U500-Vout-)") (class "Default")
      (node (ref "C503") (pin "2") (pinfunction "2_2") (pintype "passive"))
      (node (ref "JP502") (pin "3") (pinfunction "3_3") (pintype "passive"))
      (node (ref "U500") (pin "4") (pinfunction "Vout-_4") (pintype "passive"))
      (node (ref "U505") (pin "15") (pinfunction "Vdd2_15") (pintype "passive"))
      (node (ref "U505") (pin "9") (pinfunction "Vdd2_9") (pintype "passive"))
    )
    (net (code "43") (name "Net-(U501-OUT)") (class "Default")
      (node (ref "C507") (pin "2") (pinfunction "2_2") (pintype "passive"))
      (node (ref "JP501") (pin "8") (pinfunction "8_8") (pintype "passive"))
      (node (ref "U501") (pin "1") (pinfunction "OUT_1") (pintype "power_in"))
    )
    (net (code "44") (name "Net-(U502-COMP)") (class "Default")
      (node (ref "C513") (pin "2") (pinfunction "2_2") (pintype "passive"))
      (node (ref "C516") (pin "2") (pinfunction "2_2") (pintype "passive"))
      (node (ref "R513") (pin "1") (pinfunction "1_1") (pintype "passive"))
      (node (ref "U502") (pin "2") (pinfunction "COMP_2") (pintype "passive"))
      (node (ref "U503") (pin "4") (pinfunction "2_4") (pintype "passive"))
    )
    (net (code "45") (name "Net-(U502-CS)") (class "Default")
      (node (ref "C515") (pin "1") (pinfunction "1_1") (pintype "passive"))
      (node (ref "R523") (pin "2") (pinfunction "2_2") (pintype "passive"))
      (node (ref "U502") (pin "4") (pinfunction "CS_4") (pintype "passive"))
    )
    (net (code "46") (name "Net-(U502-GD)") (class "Default")
      (node (ref "R522") (pin "2") (pinfunction "2_2") (pintype "passive"))
      (node (ref "U502") (pin "7") (pinfunction "GD_7") (pintype "passive"))
    )
    (net (code "47") (name "Net-(U502-INV)") (class "Default")
      (node (ref "C513") (pin "1") (pinfunction "1_1") (pintype "passive"))
      (node (ref "R502") (pin "1") (pinfunction "1_1") (pintype "passive"))
      (node (ref "R506") (pin "2") (pinfunction "2_2") (pintype "passive"))
      (node (ref "R513") (pin "2") (pinfunction "2_2") (pintype "passive"))
      (node (ref "U502") (pin "1") (pinfunction "INV_1") (pintype "passive"))
    )
    (net (code "48") (name "Net-(U502-UFF)") (class "Default")
      (node (ref "C514") (pin "1") (pinfunction "1_1") (pintype "passive"))
      (node (ref "R517") (pin "1") (pinfunction "1_1") (pintype "passive"))
      (node (ref "R524") (pin "2") (pinfunction "2_2") (pintype "passive"))
      (node (ref "U502") (pin "3") (pinfunction "UFF_3") (pintype "passive"))
    )
    (net (code "49") (name "Net-(U503-1)") (class "Default")
      (node (ref "R530") (pin "2") (pinfunction "2_2") (pintype "passive"))
      (node (ref "U503") (pin "2") (pinfunction "1_2") (pintype "passive"))
    )
    (net (code "50") (name "Net-(U505-DE)") (class "Default")
      (node (ref "C518") (pin "2") (pinfunction "2_2") (pintype "passive"))
      (node (ref "JP501") (pin "4") (pinfunction "4_4") (pintype "passive"))
      (node (ref "U505") (pin "5") (pinfunction "DE_5") (pintype "passive"))
    )
    (net (code "51") (name "Net-(U505-PV)") (class "Default")
      (node (ref "C519") (pin "2") (pinfunction "2_2") (pintype "passive"))
      (node (ref "R531") (pin "2") (pinfunction "2_2") (pintype "passive"))
      (node (ref "U505") (pin "7") (pinfunction "PV_7") (pintype "passive"))
    )
    (net (code "52") (name "Net-(U505-RXD)") (class "Default")
      (node (ref "JP501") (pin "9") (pinfunction "9_9") (pintype "passive"))
      (node (ref "U505") (pin "3") (pinfunction "RXD_3") (pintype "passive"))
    )
    (net (code "53") (name "Net-(U505-TXD)") (class "Default")
      (node (ref "JP501") (pin "10") (pinfunction "10_10") (pintype "passive"))
      (node (ref "U505") (pin "6") (pinfunction "TXD_6") (pintype "passive"))
    )
    (net (code "54") (name "unconnected-(D511-NC-Pad4)") (class "Default")
      (node (ref "D511") (pin "4") (pinfunction "NC_4") (pintype "passive"))
    )
    (net (code "55") (name "unconnected-(D511-NC-Pad5)") (class "Default")
      (node (ref "D511") (pin "5") (pinfunction "NC_5") (pintype "passive"))
    )
    (net (code "56") (name "unconnected-(D512-NC-Pad4)") (class "Default")
      (node (ref "D512") (pin "4") (pinfunction "NC_4") (pintype "passive"))
    )
    (net (code "57") (name "unconnected-(D512-NC-Pad5)") (class "Default")
      (node (ref "D512") (pin "5") (pinfunction "NC_5") (pintype "passive"))
    )
    (net (code "58") (name "unconnected-(JP500-Pad3)") (class "Default")
      (node (ref "JP500") (pin "3") (pinfunction "3_3") (pintype "passive"))
    )
    (net (code "59") (name "unconnected-(JP500-Pad4)") (class "Default")
      (node (ref "JP500") (pin "4") (pinfunction "4_4") (pintype "passive"))
    )
    (net (code "60") (name "unconnected-(JP500-Pad5)") (class "Default")
      (node (ref "JP500") (pin "5") (pinfunction "5_5") (pintype "passive"))
    )
    (net (code "61") (name "unconnected-(JP500-Pad6)") (class "Default")
      (node (ref "JP500") (pin "6") (pinfunction "6_6") (pintype "passive"))
    )
    (net (code "62") (name "unconnected-(JP500-Pad7)") (class "Default")
      (node (ref "JP500") (pin "7") (pinfunction "7_7") (pintype "passive"))
    )
    (net (code "63") (name "unconnected-(JP500-Pad8)") (class "Default")
      (node (ref "JP500") (pin "8") (pinfunction "8_8") (pintype "passive"))
    )
    (net (code "64") (name "unconnected-(L500-Pad9)") (class "Default")
      (node (ref "L500") (pin "9") (pintype "passive"))
    )
    (net (code "65") (name "unconnected-(L500-Pad10)") (class "Default")
      (node (ref "L500") (pin "10") (pinfunction "10_10") (pintype "passive"))
    )
    (net (code "66") (name "unconnected-(U501-NC-Pad4)") (class "Default")
      (node (ref "U501") (pin "4") (pinfunction "NC_4") (pintype "passive"))
    )
    (net (code "67") (name "unconnected-(U501-NC-Pad8)") (class "Default")
      (node (ref "U501") (pin "8") (pinfunction "NC_8") (pintype "passive"))
    )
  )
)
